# STM32.net
KiCad netlist of a schematic drawn in Altium Designer
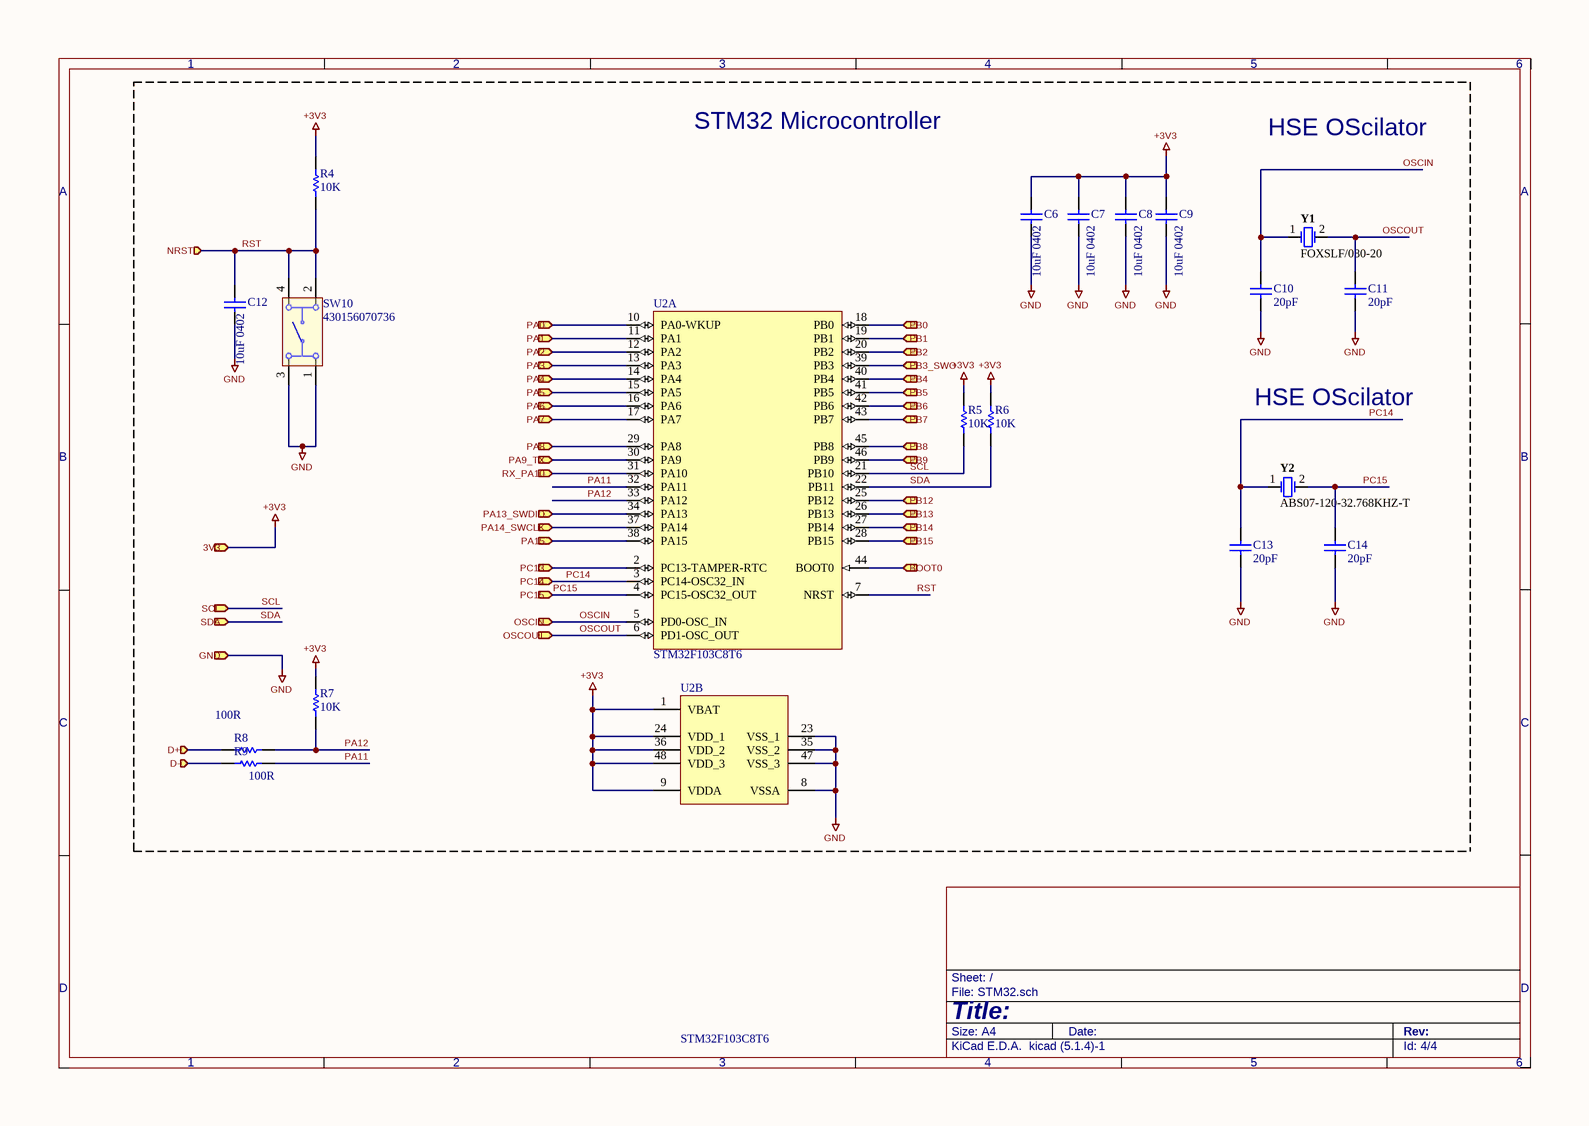
[diagram p0: STM32.SchDoc]

(export (version "E")
  (design (tool "Eeschema 10.0.6"))
  (components
    (comp (ref "C6")
      (value "10uF 0402")
      (footprint "CAPC1005X55X30ML05T10")
      (fields (field (name "MANUFACTURER") "Kemet") (field (name "PART NUMBER") "C0402C104J4RACTU"))
      (libsource (lib "Altium Content Vault") (part "CAP"))
    )
    (comp (ref "C7")
      (value "10uF 0402")
      (footprint "CAPC1005X55X30ML05T10")
      (fields (field (name "MANUFACTURER") "Kemet") (field (name "PART NUMBER") "C0402C104J4RACTU"))
      (libsource (lib "Altium Content Vault") (part "CAP"))
    )
    (comp (ref "C8")
      (value "10uF 0402")
      (footprint "CAPC1005X55X30ML05T10")
      (fields (field (name "MANUFACTURER") "Kemet") (field (name "PART NUMBER") "C0402C104J4RACTU"))
      (libsource (lib "Altium Content Vault") (part "CAP"))
    )
    (comp (ref "C9")
      (value "10uF 0402")
      (footprint "CAPC1005X55X30ML05T10")
      (fields (field (name "MANUFACTURER") "Kemet") (field (name "PART NUMBER") "C0402C104J4RACTU"))
      (libsource (lib "Altium Content Vault") (part "CAP"))
    )
    (comp (ref "C10")
      (value "20pF")
      (footprint "CAPC1005X56X25NL10T15")
      (fields
        (field (name "PART NUMBER") "04025A200JAT2A")
        (field (name "MANUFACTURER") "AVX Interconnect / Elco")
      )
      (libsource (lib "Altium Content Vault") (part "CAP"))
    )
    (comp (ref "C11")
      (value "20pF")
      (footprint "CAPC1005X56X25NL10T15")
      (fields
        (field (name "PART NUMBER") "04025A200JAT2A")
        (field (name "MANUFACTURER") "AVX Interconnect / Elco")
      )
      (libsource (lib "Altium Content Vault") (part "CAP"))
    )
    (comp (ref "C12")
      (value "10uF 0402")
      (footprint "CAPC1005X55X30ML05T10")
      (fields (field (name "MANUFACTURER") "Kemet") (field (name "PART NUMBER") "C0402C104J4RACTU"))
      (libsource (lib "Altium Content Vault") (part "CAP"))
    )
    (comp (ref "C13")
      (value "20pF")
      (footprint "CAPC1005X56X25NL10T15")
      (fields
        (field (name "PART NUMBER") "04025A200JAT2A")
        (field (name "MANUFACTURER") "AVX Interconnect / Elco")
      )
      (libsource (lib "Altium Content Vault") (part "CAP"))
    )
    (comp (ref "C14")
      (value "20pF")
      (footprint "CAPC1005X56X25NL10T15")
      (fields
        (field (name "PART NUMBER") "04025A200JAT2A")
        (field (name "MANUFACTURER") "AVX Interconnect / Elco")
      )
      (libsource (lib "Altium Content Vault") (part "CAP"))
    )
    (comp (ref "R4")
      (value "10K")
      (footprint "RESC1005X40X25NL05T05")
      (fields (field (name "MANUFACTURER") "Vishay Dale") (field (name "PART NUMBER") "CRCW0402330RFKED"))
      (libsource (lib "Altium Content Vault") (part "RES"))
    )
    (comp (ref "R5")
      (value "10K")
      (footprint "RESC1005X40X25NL05T05")
      (fields (field (name "MANUFACTURER") "Vishay Dale") (field (name "PART NUMBER") "CRCW0402330RFKED"))
      (libsource (lib "Altium Content Vault") (part "RES"))
    )
    (comp (ref "R6")
      (value "10K")
      (footprint "RESC1005X40X25NL05T05")
      (fields (field (name "MANUFACTURER") "Vishay Dale") (field (name "PART NUMBER") "CRCW0402330RFKED"))
      (libsource (lib "Altium Content Vault") (part "RES"))
    )
    (comp (ref "R7")
      (value "10K")
      (footprint "RESC1005X40X25NL05T05")
      (fields (field (name "MANUFACTURER") "Vishay Dale") (field (name "PART NUMBER") "CRCW0402330RFKED"))
      (libsource (lib "Altium Content Vault") (part "RES"))
    )
    (comp (ref "R8")
      (value "100R")
      (footprint "RESC1005X40X25NL05T05")
      (fields (field (name "MANUFACTURER") "Vishay Dale") (field (name "PART NUMBER") "CRCW0402330RFKED"))
      (libsource (lib "Altium Content Vault") (part "RES"))
    )
    (comp (ref "R9")
      (value "100R")
      (footprint "RESC1005X40X25NL05T05")
      (fields (field (name "MANUFACTURER") "Vishay Dale") (field (name "PART NUMBER") "CRCW0402330RFKED"))
      (libsource (lib "Altium Content Vault") (part "RES"))
    )
    (comp (ref "SW10")
      (value "430156070736")
      (footprint "430156070736")
      (description "WS-TATV THT Tact Switch 6X6 mm")
      (fields (field (name "MANUFACTURER") "Wuerth Elektronik"))
      (libsource (lib "Altium Content Vault") (part "WE-TACT-SW-4"))
    )
    (comp (ref "U2")
      (value "STM32F103C8T6")
      (footprint "STM-LQFP48_L")
      (libsource (lib "Altium Content Vault") (part "MC-ARM-STM32F103X8_B-SQ48"))
    )
    (comp (ref "Y1")
      (value "FOXSLF/080-20")
      (footprint "FOX-FOXSLF080-20")
      (description "Resistance Weld Thru-Hole Crystal, 8 MHz, -20 to 70 degC, 2-Pin THD, RoHS, Bulk")
      (libsource (lib "Altium Content Vault") (part "XTAL-1-2-2"))
    )
    (comp (ref "Y2")
      (value "ABS07-120-32.768KHZ-T")
      (footprint "ABRA-ABS07_A_V")
      (description "Tuning Fork Crystal, 32.768 KHz, +/- 20 ppm, -40 to 85 degC, 2-Pin SMD, RoHS, Tape and Reel")
      (fields (field (name "MANUFACTURER") "Abracon") (field (name "TOLERANCE") "20ppm"))
      (libsource (lib "Altium Content Vault") (part "XTAL-1-2-2"))
    )
  )
  (nets
    (net (code "1") (name "+3V3") (class "Default")
      (node (ref "C6") (pin "2") (pinfunction "2_2") (pintype "passive"))
      (node (ref "C7") (pin "2") (pinfunction "2_2") (pintype "passive"))
      (node (ref "C8") (pin "2") (pinfunction "2_2") (pintype "passive"))
      (node (ref "C9") (pin "2") (pinfunction "2_2") (pintype "passive"))
      (node (ref "R4") (pin "2") (pinfunction "2_2") (pintype "passive"))
      (node (ref "R5") (pin "2") (pinfunction "2_2") (pintype "passive"))
      (node (ref "R6") (pin "2") (pinfunction "2_2") (pintype "passive"))
      (node (ref "R7") (pin "2") (pinfunction "2_2") (pintype "passive"))
      (node (ref "U2") (pin "1") (pinfunction "VBAT_1") (pintype "power_in"))
      (node (ref "U2") (pin "24") (pinfunction "VDD_1_24") (pintype "power_in"))
      (node (ref "U2") (pin "36") (pinfunction "VDD_2_36") (pintype "power_in"))
      (node (ref "U2") (pin "48") (pinfunction "VDD_3_48") (pintype "power_in"))
      (node (ref "U2") (pin "9") (pinfunction "VDDA_9") (pintype "power_in"))
    )
    (net (code "2") (name "/BOOT0") (class "Default")
      (node (ref "U2") (pin "44") (pinfunction "BOOT0_44") (pintype "input"))
    )
    (net (code "3") (name "/D+") (class "Default")
      (node (ref "R8") (pin "2") (pinfunction "2_2") (pintype "passive"))
    )
    (net (code "4") (name "/D-") (class "Default")
      (node (ref "R9") (pin "2") (pinfunction "2_2") (pintype "passive"))
    )
    (net (code "5") (name "/OSCIN") (class "Default")
      (node (ref "C10") (pin "2") (pinfunction "2_2") (pintype "passive"))
      (node (ref "U2") (pin "5") (pinfunction "PD0-OSC_IN_5") (pintype "bidirectional"))
      (node (ref "Y1") (pin "1") (pinfunction "1_1") (pintype "passive"))
    )
    (net (code "6") (name "/OSCOUT") (class "Default")
      (node (ref "C11") (pin "2") (pinfunction "2_2") (pintype "passive"))
      (node (ref "U2") (pin "6") (pinfunction "PD1-OSC_OUT_6") (pintype "bidirectional"))
      (node (ref "Y1") (pin "2") (pinfunction "2_2") (pintype "passive"))
    )
    (net (code "7") (name "/PA0") (class "Default")
      (node (ref "U2") (pin "10") (pinfunction "PA0-WKUP_10") (pintype "bidirectional"))
    )
    (net (code "8") (name "/PA1") (class "Default")
      (node (ref "U2") (pin "11") (pinfunction "PA1_11") (pintype "bidirectional"))
    )
    (net (code "9") (name "/PA2") (class "Default")
      (node (ref "U2") (pin "12") (pinfunction "PA2_12") (pintype "bidirectional"))
    )
    (net (code "10") (name "/PA3") (class "Default")
      (node (ref "U2") (pin "13") (pinfunction "PA3_13") (pintype "bidirectional"))
    )
    (net (code "11") (name "/PA4") (class "Default")
      (node (ref "U2") (pin "14") (pinfunction "PA4_14") (pintype "bidirectional"))
    )
    (net (code "12") (name "/PA5") (class "Default")
      (node (ref "U2") (pin "15") (pinfunction "PA5_15") (pintype "bidirectional"))
    )
    (net (code "13") (name "/PA6") (class "Default")
      (node (ref "U2") (pin "16") (pinfunction "PA6_16") (pintype "bidirectional"))
    )
    (net (code "14") (name "/PA7") (class "Default")
      (node (ref "U2") (pin "17") (pinfunction "PA7_17") (pintype "bidirectional"))
    )
    (net (code "15") (name "/PA8") (class "Default")
      (node (ref "U2") (pin "29") (pinfunction "PA8_29") (pintype "bidirectional"))
    )
    (net (code "16") (name "/PA9_TX") (class "Default")
      (node (ref "U2") (pin "30") (pinfunction "PA9_30") (pintype "bidirectional"))
    )
    (net (code "17") (name "/PA11") (class "Default")
      (node (ref "R9") (pin "1") (pinfunction "1_1") (pintype "passive"))
      (node (ref "U2") (pin "32") (pinfunction "PA11_32") (pintype "bidirectional"))
    )
    (net (code "18") (name "/PA12") (class "Default")
      (node (ref "R7") (pin "1") (pinfunction "1_1") (pintype "passive"))
      (node (ref "R8") (pin "1") (pinfunction "1_1") (pintype "passive"))
      (node (ref "U2") (pin "33") (pinfunction "PA12_33") (pintype "bidirectional"))
    )
    (net (code "19") (name "/PA13_SWDIO") (class "Default")
      (node (ref "U2") (pin "34") (pinfunction "PA13_34") (pintype "bidirectional"))
    )
    (net (code "20") (name "/PA14_SWCLK") (class "Default")
      (node (ref "U2") (pin "37") (pinfunction "PA14_37") (pintype "bidirectional"))
    )
    (net (code "21") (name "/PA15") (class "Default")
      (node (ref "U2") (pin "38") (pinfunction "PA15_38") (pintype "bidirectional"))
    )
    (net (code "22") (name "/PB0") (class "Default")
      (node (ref "U2") (pin "18") (pinfunction "PB0_18") (pintype "bidirectional"))
    )
    (net (code "23") (name "/PB1") (class "Default")
      (node (ref "U2") (pin "19") (pinfunction "PB1_19") (pintype "bidirectional"))
    )
    (net (code "24") (name "/PB2") (class "Default")
      (node (ref "U2") (pin "20") (pinfunction "PB2_20") (pintype "bidirectional"))
    )
    (net (code "25") (name "/PB3_SWO") (class "Default")
      (node (ref "U2") (pin "39") (pinfunction "PB3_39") (pintype "bidirectional"))
    )
    (net (code "26") (name "/PB4") (class "Default")
      (node (ref "U2") (pin "40") (pinfunction "PB4_40") (pintype "bidirectional"))
    )
    (net (code "27") (name "/PB5") (class "Default")
      (node (ref "U2") (pin "41") (pinfunction "PB5_41") (pintype "bidirectional"))
    )
    (net (code "28") (name "/PB6") (class "Default")
      (node (ref "U2") (pin "42") (pinfunction "PB6_42") (pintype "bidirectional"))
    )
    (net (code "29") (name "/PB7") (class "Default")
      (node (ref "U2") (pin "43") (pinfunction "PB7_43") (pintype "bidirectional"))
    )
    (net (code "30") (name "/PB8") (class "Default")
      (node (ref "U2") (pin "45") (pinfunction "PB8_45") (pintype "bidirectional"))
    )
    (net (code "31") (name "/PB9") (class "Default")
      (node (ref "U2") (pin "46") (pinfunction "PB9_46") (pintype "bidirectional"))
    )
    (net (code "32") (name "/PB12") (class "Default")
      (node (ref "U2") (pin "25") (pinfunction "PB12_25") (pintype "bidirectional"))
    )
    (net (code "33") (name "/PB13") (class "Default")
      (node (ref "U2") (pin "26") (pinfunction "PB13_26") (pintype "bidirectional"))
    )
    (net (code "34") (name "/PB14") (class "Default")
      (node (ref "U2") (pin "27") (pinfunction "PB14_27") (pintype "bidirectional"))
    )
    (net (code "35") (name "/PB15") (class "Default")
      (node (ref "U2") (pin "28") (pinfunction "PB15_28") (pintype "bidirectional"))
    )
    (net (code "36") (name "/PC13") (class "Default")
      (node (ref "U2") (pin "2") (pinfunction "PC13-TAMPER-RTC_2") (pintype "bidirectional"))
    )
    (net (code "37") (name "/PC14") (class "Default")
      (node (ref "C13") (pin "2") (pinfunction "2_2") (pintype "passive"))
      (node (ref "U2") (pin "3") (pinfunction "PC14-OSC32_IN_3") (pintype "bidirectional"))
      (node (ref "Y2") (pin "1") (pinfunction "1_1") (pintype "passive"))
    )
    (net (code "38") (name "/PC15") (class "Default")
      (node (ref "C14") (pin "2") (pinfunction "2_2") (pintype "passive"))
      (node (ref "U2") (pin "4") (pinfunction "PC15-OSC32_OUT_4") (pintype "bidirectional"))
      (node (ref "Y2") (pin "2") (pinfunction "2_2") (pintype "passive"))
    )
    (net (code "39") (name "/RST") (class "Default")
      (node (ref "C12") (pin "2") (pinfunction "2_2") (pintype "passive"))
      (node (ref "R4") (pin "1") (pinfunction "1_1") (pintype "passive"))
      (node (ref "SW10") (pin "2") (pinfunction "2_2") (pintype "passive"))
      (node (ref "SW10") (pin "4") (pinfunction "4_4") (pintype "passive"))
      (node (ref "U2") (pin "7") (pinfunction "NRST_7") (pintype "bidirectional"))
    )
    (net (code "40") (name "/RX_PA10") (class "Default")
      (node (ref "U2") (pin "31") (pinfunction "PA10_31") (pintype "bidirectional"))
    )
    (net (code "41") (name "/SCL") (class "Default")
      (node (ref "R5") (pin "1") (pinfunction "1_1") (pintype "passive"))
      (node (ref "U2") (pin "21") (pinfunction "PB10_21") (pintype "bidirectional"))
    )
    (net (code "42") (name "/SDA") (class "Default")
      (node (ref "R6") (pin "1") (pinfunction "1_1") (pintype "passive"))
      (node (ref "U2") (pin "22") (pinfunction "PB11_22") (pintype "bidirectional"))
    )
    (net (code "43") (name "GND") (class "Default")
      (node (ref "C10") (pin "1") (pinfunction "1_1") (pintype "passive"))
      (node (ref "C11") (pin "1") (pinfunction "1_1") (pintype "passive"))
      (node (ref "C12") (pin "1") (pinfunction "1_1") (pintype "passive"))
      (node (ref "C13") (pin "1") (pinfunction "1_1") (pintype "passive"))
      (node (ref "C14") (pin "1") (pinfunction "1_1") (pintype "passive"))
      (node (ref "C6") (pin "1") (pinfunction "1_1") (pintype "passive"))
      (node (ref "C7") (pin "1") (pinfunction "1_1") (pintype "passive"))
      (node (ref "C8") (pin "1") (pinfunction "1_1") (pintype "passive"))
      (node (ref "C9") (pin "1") (pinfunction "1_1") (pintype "passive"))
      (node (ref "SW10") (pin "1") (pinfunction "1_1") (pintype "passive"))
      (node (ref "SW10") (pin "3") (pinfunction "3_3") (pintype "passive"))
      (node (ref "U2") (pin "23") (pinfunction "VSS_1_23") (pintype "power_in"))
      (node (ref "U2") (pin "35") (pinfunction "VSS_2_35") (pintype "power_in"))
      (node (ref "U2") (pin "47") (pinfunction "VSS_3_47") (pintype "power_in"))
      (node (ref "U2") (pin "8") (pinfunction "VSSA_8") (pintype "power_in"))
    )
  )
)
